# Papaiz.net
KiCad netlist of a schematic drawn in EAGLE
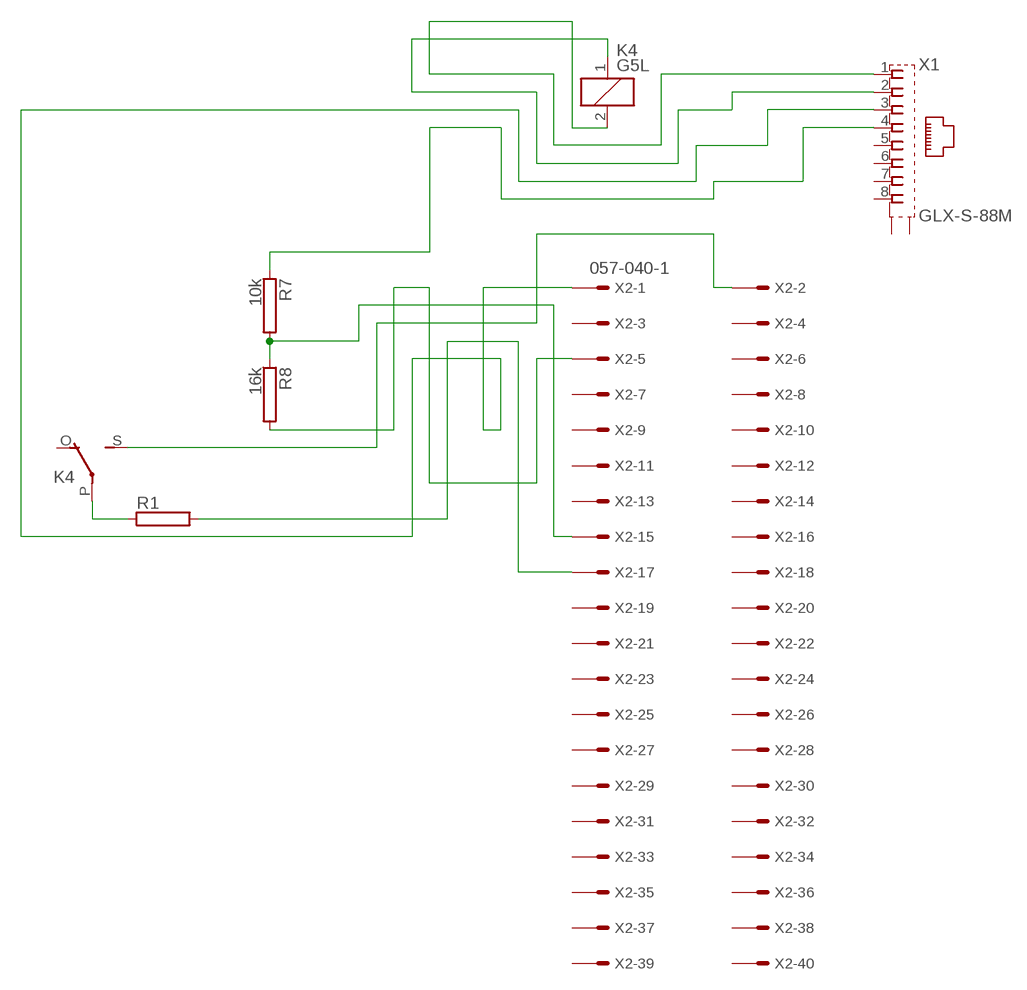
[diagram p0: schematic, sheet 1]

(export (version "E")
  (design (tool "Eeschema 10.0.6"))
  (components
    (comp (ref "K4")
      (value "G5L")
      (footprint "eagle-import:G5LE")
      (libsource (lib "eagle-import") (part "G5L"))
    )
    (comp (ref "R1")
      (value "RAC01")
      (footprint "eagle-import:AC01")
      (libsource (lib "eagle-import") (part "RAC01"))
    )
    (comp (ref "R7")
      (value "10k")
      (footprint "eagle-import:AC01")
      (libsource (lib "eagle-import") (part "RAC01"))
    )
    (comp (ref "R8")
      (value "16k")
      (footprint "eagle-import:AC01")
      (libsource (lib "eagle-import") (part "RAC01"))
    )
    (comp (ref "X1")
      (value "GLX-S-88M")
      (footprint "eagle-import:GLX-S-88M")
      (libsource (lib "eagle-import") (part "GLX-S-88M"))
    )
    (comp (ref "X2")
      (value "057-040-1")
      (footprint "eagle-import:057-040-1")
      (libsource (lib "eagle-import") (part "057-040-1"))
    )
  )
  (nets
    (net (code "1") (name "Net-(K4-Pad1)") (class "Default")
      (node (ref "K4") (pin "1") (pinfunction "1_1") (pintype "passive"))
      (node (ref "X1") (pin "2") (pinfunction "2_2") (pintype "passive"))
    )
    (net (code "2") (name "Net-(K4-Pad2)") (class "Default")
      (node (ref "K4") (pin "2") (pinfunction "2_2") (pintype "passive"))
      (node (ref "X1") (pin "1") (pinfunction "1_1") (pintype "passive"))
    )
    (net (code "3") (name "Net-(K4-PadP)") (class "Default")
      (node (ref "K4") (pin "P") (pinfunction "P_P") (pintype "passive"))
      (node (ref "R1") (pin "1") (pinfunction "1_1") (pintype "passive"))
    )
    (net (code "4") (name "Net-(R7-Pad1)") (class "Default")
      (node (ref "R7") (pin "1") (pinfunction "1_1") (pintype "passive"))
      (node (ref "X1") (pin "4") (pinfunction "4_4") (pintype "passive"))
    )
    (net (code "5") (name "Net-(X2A-S)") (class "Default")
      (node (ref "X1") (pin "3") (pinfunction "3_3") (pintype "passive"))
      (node (ref "X2") (pin "1") (pinfunction "S_1") (pintype "passive"))
    )
    (net (code "6") (name "Net-(X2AJ-S)") (class "Default")
      (node (ref "R8") (pin "2") (pinfunction "2_2") (pintype "passive"))
      (node (ref "X2") (pin "5") (pinfunction "S_5") (pintype "passive"))
    )
    (net (code "7") (name "Net-(X2G-S)") (class "Default")
      (node (ref "R7") (pin "2") (pinfunction "2_2") (pintype "passive"))
      (node (ref "R8") (pin "1") (pinfunction "1_1") (pintype "passive"))
      (node (ref "X2") (pin "15") (pinfunction "S_15") (pintype "passive"))
    )
    (net (code "8") (name "Net-(X2I-S)") (class "Default")
      (node (ref "R1") (pin "2") (pinfunction "2_2") (pintype "passive"))
      (node (ref "X2") (pin "17") (pinfunction "S_17") (pintype "passive"))
    )
    (net (code "9") (name "Net-(X2L-S)") (class "Default")
      (node (ref "K4") (pin "S") (pinfunction "S_S") (pintype "passive"))
      (node (ref "X2") (pin "2") (pinfunction "S_2") (pintype "passive"))
    )
    (net (code "10") (name "unconnected-(K4-PadO)") (class "Default")
      (node (ref "K4") (pin "O") (pinfunction "O_O") (pintype "passive"))
    )
    (net (code "11") (name "unconnected-(X1-Pad5)") (class "Default")
      (node (ref "X1") (pin "5") (pinfunction "5_5") (pintype "passive"))
    )
    (net (code "12") (name "unconnected-(X1-Pad6)") (class "Default")
      (node (ref "X1") (pin "6") (pinfunction "6_6") (pintype "passive"))
    )
    (net (code "13") (name "unconnected-(X1-Pad7)") (class "Default")
      (node (ref "X1") (pin "7") (pinfunction "7_7") (pintype "passive"))
    )
    (net (code "14") (name "unconnected-(X1-Pad8)") (class "Default")
      (node (ref "X1") (pin "8") (pinfunction "8_8") (pintype "passive"))
    )
    (net (code "15") (name "unconnected-(X1-PadS1)") (class "Default")
      (node (ref "X1") (pin "S1") (pinfunction "S1_S1") (pintype "passive"))
    )
    (net (code "16") (name "unconnected-(X1-PadS2)") (class "Default")
      (node (ref "X1") (pin "S2") (pinfunction "S2_S2") (pintype "passive"))
    )
    (net (code "17") (name "unconnected-(X2AA-S-Pad33)") (class "Default")
      (node (ref "X2") (pin "33") (pinfunction "S_33") (pintype "passive"))
    )
    (net (code "18") (name "unconnected-(X2AB-S-Pad34)") (class "Default")
      (node (ref "X2") (pin "34") (pinfunction "S_34") (pintype "passive"))
    )
    (net (code "19") (name "unconnected-(X2AC-S-Pad35)") (class "Default")
      (node (ref "X2") (pin "35") (pinfunction "S_35") (pintype "passive"))
    )
    (net (code "20") (name "unconnected-(X2AD-S-Pad36)") (class "Default")
      (node (ref "X2") (pin "36") (pinfunction "S_36") (pintype "passive"))
    )
    (net (code "21") (name "unconnected-(X2AE-S-Pad37)") (class "Default")
      (node (ref "X2") (pin "37") (pinfunction "S_37") (pintype "passive"))
    )
    (net (code "22") (name "unconnected-(X2AF-S-Pad38)") (class "Default")
      (node (ref "X2") (pin "38") (pinfunction "S_38") (pintype "passive"))
    )
    (net (code "23") (name "unconnected-(X2AG-S-Pad39)") (class "Default")
      (node (ref "X2") (pin "39") (pinfunction "S_39") (pintype "passive"))
    )
    (net (code "24") (name "unconnected-(X2AH-S-Pad4)") (class "Default")
      (node (ref "X2") (pin "4") (pinfunction "S_4") (pintype "passive"))
    )
    (net (code "25") (name "unconnected-(X2AI-S-Pad40)") (class "Default")
      (node (ref "X2") (pin "40") (pinfunction "S_40") (pintype "passive"))
    )
    (net (code "26") (name "unconnected-(X2AK-S-Pad6)") (class "Default")
      (node (ref "X2") (pin "6") (pinfunction "S_6") (pintype "passive"))
    )
    (net (code "27") (name "unconnected-(X2AL-S-Pad7)") (class "Default")
      (node (ref "X2") (pin "7") (pinfunction "S_7") (pintype "passive"))
    )
    (net (code "28") (name "unconnected-(X2AM-S-Pad8)") (class "Default")
      (node (ref "X2") (pin "8") (pinfunction "S_8") (pintype "passive"))
    )
    (net (code "29") (name "unconnected-(X2AN-S-Pad9)") (class "Default")
      (node (ref "X2") (pin "9") (pinfunction "S_9") (pintype "passive"))
    )
    (net (code "30") (name "unconnected-(X2B-S-Pad10)") (class "Default")
      (node (ref "X2") (pin "10") (pinfunction "S_10") (pintype "passive"))
    )
    (net (code "31") (name "unconnected-(X2C-S-Pad11)") (class "Default")
      (node (ref "X2") (pin "11") (pinfunction "S_11") (pintype "passive"))
    )
    (net (code "32") (name "unconnected-(X2D-S-Pad12)") (class "Default")
      (node (ref "X2") (pin "12") (pinfunction "S_12") (pintype "passive"))
    )
    (net (code "33") (name "unconnected-(X2E-S-Pad13)") (class "Default")
      (node (ref "X2") (pin "13") (pinfunction "S_13") (pintype "passive"))
    )
    (net (code "34") (name "unconnected-(X2F-S-Pad14)") (class "Default")
      (node (ref "X2") (pin "14") (pinfunction "S_14") (pintype "passive"))
    )
    (net (code "35") (name "unconnected-(X2H-S-Pad16)") (class "Default")
      (node (ref "X2") (pin "16") (pinfunction "S_16") (pintype "passive"))
    )
    (net (code "36") (name "unconnected-(X2J-S-Pad18)") (class "Default")
      (node (ref "X2") (pin "18") (pinfunction "S_18") (pintype "passive"))
    )
    (net (code "37") (name "unconnected-(X2K-S-Pad19)") (class "Default")
      (node (ref "X2") (pin "19") (pinfunction "S_19") (pintype "passive"))
    )
    (net (code "38") (name "unconnected-(X2M-S-Pad20)") (class "Default")
      (node (ref "X2") (pin "20") (pinfunction "S_20") (pintype "passive"))
    )
    (net (code "39") (name "unconnected-(X2N-S-Pad21)") (class "Default")
      (node (ref "X2") (pin "21") (pinfunction "S_21") (pintype "passive"))
    )
    (net (code "40") (name "unconnected-(X2O-S-Pad22)") (class "Default")
      (node (ref "X2") (pin "22") (pinfunction "S_22") (pintype "passive"))
    )
    (net (code "41") (name "unconnected-(X2P-S-Pad23)") (class "Default")
      (node (ref "X2") (pin "23") (pinfunction "S_23") (pintype "passive"))
    )
    (net (code "42") (name "unconnected-(X2Q-S-Pad24)") (class "Default")
      (node (ref "X2") (pin "24") (pinfunction "S_24") (pintype "passive"))
    )
    (net (code "43") (name "unconnected-(X2R-S-Pad25)") (class "Default")
      (node (ref "X2") (pin "25") (pinfunction "S_25") (pintype "passive"))
    )
    (net (code "44") (name "unconnected-(X2S-S-Pad26)") (class "Default")
      (node (ref "X2") (pin "26") (pinfunction "S_26") (pintype "passive"))
    )
    (net (code "45") (name "unconnected-(X2T-S-Pad27)") (class "Default")
      (node (ref "X2") (pin "27") (pinfunction "S_27") (pintype "passive"))
    )
    (net (code "46") (name "unconnected-(X2U-S-Pad28)") (class "Default")
      (node (ref "X2") (pin "28") (pinfunction "S_28") (pintype "passive"))
    )
    (net (code "47") (name "unconnected-(X2V-S-Pad29)") (class "Default")
      (node (ref "X2") (pin "29") (pinfunction "S_29") (pintype "passive"))
    )
    (net (code "48") (name "unconnected-(X2W-S-Pad3)") (class "Default")
      (node (ref "X2") (pin "3") (pinfunction "S_3") (pintype "passive"))
    )
    (net (code "49") (name "unconnected-(X2X-S-Pad30)") (class "Default")
      (node (ref "X2") (pin "30") (pinfunction "S_30") (pintype "passive"))
    )
    (net (code "50") (name "unconnected-(X2Y-S-Pad31)") (class "Default")
      (node (ref "X2") (pin "31") (pinfunction "S_31") (pintype "passive"))
    )
    (net (code "51") (name "unconnected-(X2Z-S-Pad32)") (class "Default")
      (node (ref "X2") (pin "32") (pinfunction "S_32") (pintype "passive"))
    )
  )
)
